# 02_-_Module_Connector.net
KiCad netlist of a schematic drawn in Altium Designer
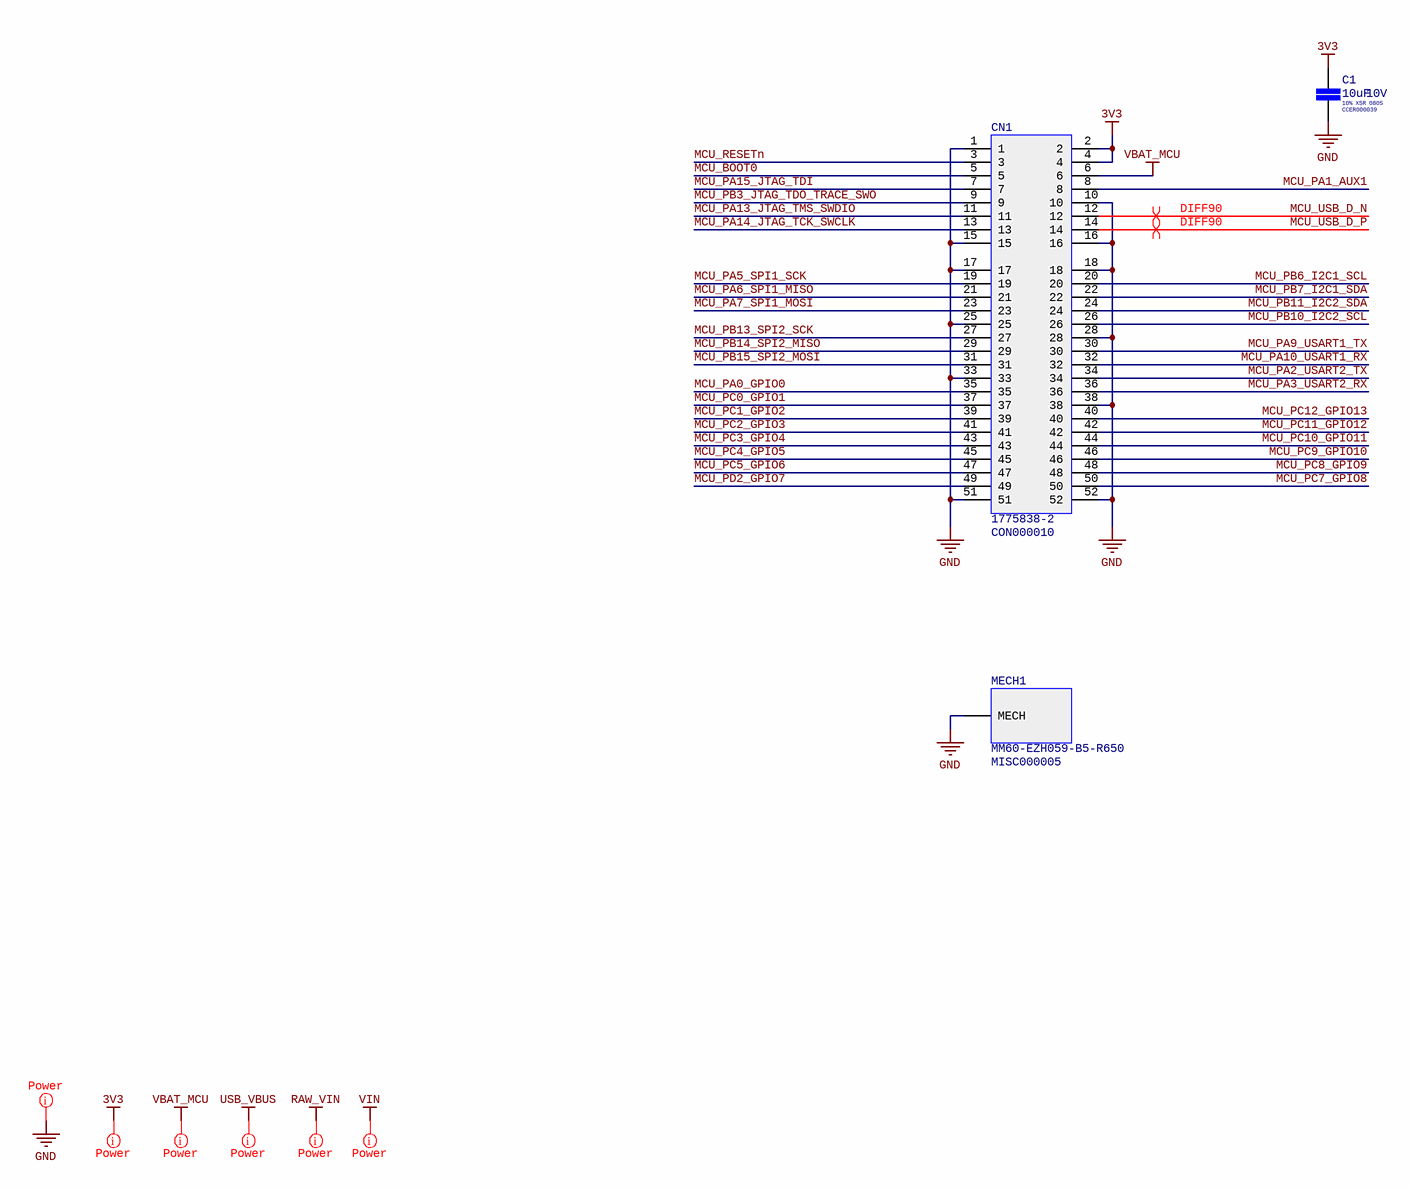
[diagram p0: [02] - Module Connector.SchDoc]

(export (version "E")
  (design (tool "Eeschema 10.0.6"))
  (components
    (comp (ref "C1")
      (value "10uF 10V")
      (footprint "CAP-SMD-0805-1.35MM-IPC-MED")
      (description "CAP CER 10U 10V X5R 10% SMD 0805 85C SAMSUNG")
      (fields
        (field (name "VOLTAGE") "10V")
        (field (name "INTERNAL PART NUMBER") "CCER000039")
        (field (name "TOLERANCE") "10%")
        (field (name "VOLTAGE RATING") "10V")
        (field (name "DIELECTRIC") "X5R")
        (field (name "CASE/PACKAGE") "0805")
        (field (name "CAPACITANCE") "10uF")
      )
      (libsource (lib "Altium_Lib_Standard") (part "CL21A106KPFNNNG"))
    )
    (comp (ref "CN1")
      (value "1775838-2")
      (footprint "CON-SMD-PCIE-MINI-52POS-1775838-2-TE")
      (description "CON MINI PCIE CARD EDGE 52POS SMD")
      (fields (field (name "INTERNAL PART NUMBER") "CON000010"))
      (libsource (lib "Altium_Lib_Standard") (part "1775838-2"))
    )
    (comp (ref "MECH1")
      (value "MM60-EZH059-B5-R650")
      (footprint "CON-SMD-PCIE-MINI-LATCH-0POS-MM60-EZH059-B5-R650-JAE")
      (description "CARD LATCH MINI PCIE 3.05mm HEIGHT")
      (fields
        (field (name "MANUFACTURER") "JAE Electronics")
        (field (name "INTERNAL PART NUMBER") "MISC000005")
      )
      (libsource (lib "Altium_Lib_Standard") (part "MM60-EZH059-B5-R650"))
    )
  )
  (nets
    (net (code "1") (name "/MCU_BOOT0") (class "Default")
      (node (ref "CN1") (pin "5") (pinfunction "5_5") (pintype "passive"))
    )
    (net (code "2") (name "/MCU_PA0_GPIO0") (class "Default")
      (node (ref "CN1") (pin "35") (pinfunction "35_35") (pintype "passive"))
    )
    (net (code "3") (name "/MCU_PA1_AUX1") (class "Default")
      (node (ref "CN1") (pin "8") (pinfunction "8_8") (pintype "passive"))
    )
    (net (code "4") (name "/MCU_PA2_USART2_TX") (class "Default")
      (node (ref "CN1") (pin "34") (pinfunction "34_34") (pintype "passive"))
    )
    (net (code "5") (name "/MCU_PA3_USART2_RX") (class "Default")
      (node (ref "CN1") (pin "36") (pinfunction "36_36") (pintype "passive"))
    )
    (net (code "6") (name "/MCU_PA5_SPI1_SCK") (class "Default")
      (node (ref "CN1") (pin "19") (pinfunction "19_19") (pintype "passive"))
    )
    (net (code "7") (name "/MCU_PA6_SPI1_MISO") (class "Default")
      (node (ref "CN1") (pin "21") (pinfunction "21_21") (pintype "passive"))
    )
    (net (code "8") (name "/MCU_PA7_SPI1_MOSI") (class "Default")
      (node (ref "CN1") (pin "23") (pinfunction "23_23") (pintype "passive"))
    )
    (net (code "9") (name "/MCU_PA9_USART1_TX") (class "Default")
      (node (ref "CN1") (pin "30") (pinfunction "30_30") (pintype "passive"))
    )
    (net (code "10") (name "/MCU_PA10_USART1_RX") (class "Default")
      (node (ref "CN1") (pin "32") (pinfunction "32_32") (pintype "passive"))
    )
    (net (code "11") (name "/MCU_PA13_JTAG_TMS_SWDIO") (class "Default")
      (node (ref "CN1") (pin "11") (pinfunction "11_11") (pintype "passive"))
    )
    (net (code "12") (name "/MCU_PA14_JTAG_TCK_SWCLK") (class "Default")
      (node (ref "CN1") (pin "13") (pinfunction "13_13") (pintype "passive"))
    )
    (net (code "13") (name "/MCU_PA15_JTAG_TDI") (class "Default")
      (node (ref "CN1") (pin "7") (pinfunction "7_7") (pintype "passive"))
    )
    (net (code "14") (name "/MCU_PB3_JTAG_TDO_TRACE_SWO") (class "Default")
      (node (ref "CN1") (pin "9") (pinfunction "9_9") (pintype "passive"))
    )
    (net (code "15") (name "/MCU_PB6_I2C1_SCL") (class "Default")
      (node (ref "CN1") (pin "20") (pinfunction "20_20") (pintype "passive"))
    )
    (net (code "16") (name "/MCU_PB7_I2C1_SDA") (class "Default")
      (node (ref "CN1") (pin "22") (pinfunction "22_22") (pintype "passive"))
    )
    (net (code "17") (name "/MCU_PB10_I2C2_SCL") (class "Default")
      (node (ref "CN1") (pin "26") (pinfunction "26_26") (pintype "passive"))
    )
    (net (code "18") (name "/MCU_PB11_I2C2_SDA") (class "Default")
      (node (ref "CN1") (pin "24") (pinfunction "24_24") (pintype "passive"))
    )
    (net (code "19") (name "/MCU_PB13_SPI2_SCK") (class "Default")
      (node (ref "CN1") (pin "27") (pinfunction "27_27") (pintype "passive"))
    )
    (net (code "20") (name "/MCU_PB14_SPI2_MISO") (class "Default")
      (node (ref "CN1") (pin "29") (pinfunction "29_29") (pintype "passive"))
    )
    (net (code "21") (name "/MCU_PB15_SPI2_MOSI") (class "Default")
      (node (ref "CN1") (pin "31") (pinfunction "31_31") (pintype "passive"))
    )
    (net (code "22") (name "/MCU_PC0_GPIO1") (class "Default")
      (node (ref "CN1") (pin "37") (pinfunction "37_37") (pintype "passive"))
    )
    (net (code "23") (name "/MCU_PC1_GPIO2") (class "Default")
      (node (ref "CN1") (pin "39") (pinfunction "39_39") (pintype "passive"))
    )
    (net (code "24") (name "/MCU_PC2_GPIO3") (class "Default")
      (node (ref "CN1") (pin "41") (pinfunction "41_41") (pintype "passive"))
    )
    (net (code "25") (name "/MCU_PC3_GPIO4") (class "Default")
      (node (ref "CN1") (pin "43") (pinfunction "43_43") (pintype "passive"))
    )
    (net (code "26") (name "/MCU_PC4_GPIO5") (class "Default")
      (node (ref "CN1") (pin "45") (pinfunction "45_45") (pintype "passive"))
    )
    (net (code "27") (name "/MCU_PC5_GPIO6") (class "Default")
      (node (ref "CN1") (pin "47") (pinfunction "47_47") (pintype "passive"))
    )
    (net (code "28") (name "/MCU_PC7_GPIO8") (class "Default")
      (node (ref "CN1") (pin "50") (pinfunction "50_50") (pintype "passive"))
    )
    (net (code "29") (name "/MCU_PC8_GPIO9") (class "Default")
      (node (ref "CN1") (pin "48") (pinfunction "48_48") (pintype "passive"))
    )
    (net (code "30") (name "/MCU_PC9_GPIO10") (class "Default")
      (node (ref "CN1") (pin "46") (pinfunction "46_46") (pintype "passive"))
    )
    (net (code "31") (name "/MCU_PC10_GPIO11") (class "Default")
      (node (ref "CN1") (pin "44") (pinfunction "44_44") (pintype "passive"))
    )
    (net (code "32") (name "/MCU_PC11_GPIO12") (class "Default")
      (node (ref "CN1") (pin "42") (pinfunction "42_42") (pintype "passive"))
    )
    (net (code "33") (name "/MCU_PC12_GPIO13") (class "Default")
      (node (ref "CN1") (pin "40") (pinfunction "40_40") (pintype "passive"))
    )
    (net (code "34") (name "/MCU_PD2_GPIO7") (class "Default")
      (node (ref "CN1") (pin "49") (pinfunction "49_49") (pintype "passive"))
    )
    (net (code "35") (name "/MCU_RESETn") (class "Default")
      (node (ref "CN1") (pin "3") (pinfunction "3_3") (pintype "passive"))
    )
    (net (code "36") (name "/MCU_USB_D_N") (class "Default")
      (node (ref "CN1") (pin "12") (pinfunction "12_12") (pintype "passive"))
    )
    (net (code "37") (name "/MCU_USB_D_P") (class "Default")
      (node (ref "CN1") (pin "14") (pinfunction "14_14") (pintype "passive"))
    )
    (net (code "38") (name "3V3") (class "Default")
      (node (ref "C1") (pin "1") (pinfunction "1_1") (pintype "passive"))
      (node (ref "CN1") (pin "2") (pinfunction "2_2") (pintype "passive"))
      (node (ref "CN1") (pin "4") (pinfunction "4_4") (pintype "passive"))
    )
    (net (code "39") (name "GND") (class "Default")
      (node (ref "C1") (pin "2") (pinfunction "2_2") (pintype "passive"))
      (node (ref "CN1") (pin "1") (pinfunction "1_1") (pintype "passive"))
      (node (ref "CN1") (pin "10") (pinfunction "10_10") (pintype "passive"))
      (node (ref "CN1") (pin "15") (pinfunction "15_15") (pintype "passive"))
      (node (ref "CN1") (pin "16") (pinfunction "16_16") (pintype "passive"))
      (node (ref "CN1") (pin "17") (pinfunction "17_17") (pintype "passive"))
      (node (ref "CN1") (pin "18") (pinfunction "18_18") (pintype "passive"))
      (node (ref "CN1") (pin "25") (pinfunction "25_25") (pintype "passive"))
      (node (ref "CN1") (pin "28") (pinfunction "28_28") (pintype "passive"))
      (node (ref "CN1") (pin "33") (pinfunction "33_33") (pintype "passive"))
      (node (ref "CN1") (pin "38") (pinfunction "38_38") (pintype "passive"))
      (node (ref "CN1") (pin "51") (pinfunction "51_51") (pintype "passive"))
      (node (ref "CN1") (pin "52") (pinfunction "52_52") (pintype "passive"))
      (node (ref "MECH1") (pin "0") (pinfunction "MECH_0") (pintype "passive"))
    )
    (net (code "42") (name "VBAT_MCU") (class "Default")
      (node (ref "CN1") (pin "6") (pinfunction "6_6") (pintype "passive"))
    )
  )
)
